# RGB_LED_Beta1.net
KiCad netlist of a schematic drawn in Altium Designer
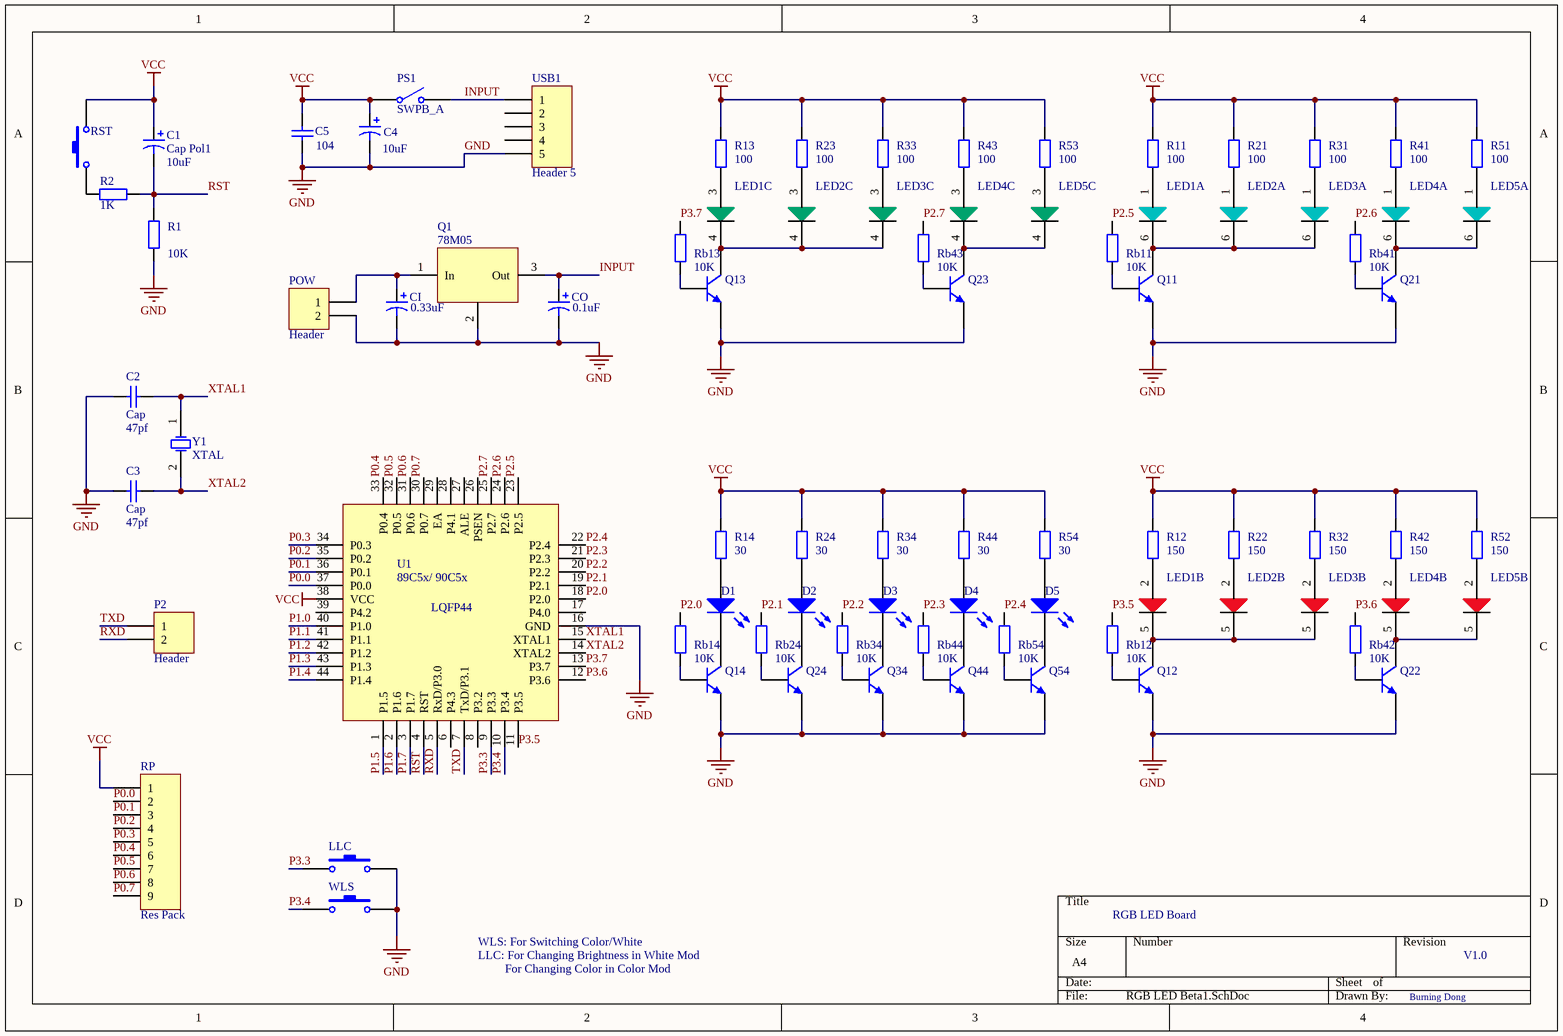
[diagram p0: RGB LED Beta1.SchDoc]

(export (version "E")
  (design (tool "Eeschema 10.0.6"))
  (components
    (comp (ref "C1")
      (value "Cap Pol1")
      (footprint "C0805")
      (description "Polarized Capacitor (Radial)")
      (fields (field (name "ALTIUM_VALUE") "10uF") (field (name "PUBLISHER") "Altium Limited"))
      (libsource (lib "Miscellaneous Devices") (part "Cap Pol1"))
    )
    (comp (ref "C2")
      (value "Cap")
      (footprint "C0805")
      (description "Capacitor")
      (fields (field (name "ALTIUM_VALUE") "47pf") (field (name "PUBLISHER") "Altium Limited"))
      (libsource (lib "Miscellaneous Devices") (part "Cap"))
    )
    (comp (ref "C3")
      (value "Cap")
      (footprint "C0805")
      (description "Capacitor")
      (fields (field (name "ALTIUM_VALUE") "47pf") (field (name "PUBLISHER") "Altium Limited"))
      (libsource (lib "Miscellaneous Devices") (part "Cap"))
    )
    (comp (ref "C4")
      (value "10uF")
      (footprint "C0805")
      (description "Polarized Capacitor (Radial)")
      (fields (field (name "Comment") "Cap Pol1") (field (name "PUBLISHER") "Altium Limited"))
      (libsource (lib "Miscellaneous Devices") (part "Cap Pol1"))
    )
    (comp (ref "C5")
      (value "104")
      (footprint "C1206")
      (description "Capacitor")
      (fields (field (name "Comment") "Cap") (field (name "PUBLISHER") "Altium Limited"))
      (libsource (lib "Miscellaneous Devices") (part "Cap"))
    )
    (comp (ref "CI")
      (value "0.33uF")
      (footprint "C0805")
      (description "Polarized Capacitor (Radial)")
      (fields (field (name "Comment") "Cap Pol1") (field (name "PUBLISHER") "Altium Limited"))
      (libsource (lib "Miscellaneous Devices") (part "Cap Pol1"))
    )
    (comp (ref "CO")
      (value "0.1uF")
      (footprint "C0805")
      (description "Polarized Capacitor (Radial)")
      (fields (field (name "Comment") "Cap Pol1") (field (name "PUBLISHER") "Altium Limited"))
      (libsource (lib "Miscellaneous Devices") (part "Cap Pol1"))
    )
    (comp (ref "D1")
      (value "LED0")
      (footprint "LED 5050 NoneRGB")
      (description "Typical INFRARED GaAs LED")
      (fields (field (name "PUBLISHER") "Altium Limited"))
      (libsource (lib "Miscellaneous Devices") (part "LED0"))
    )
    (comp (ref "D2")
      (value "LED0")
      (footprint "LED 5050 NoneRGB")
      (description "Typical INFRARED GaAs LED")
      (fields (field (name "PUBLISHER") "Altium Limited"))
      (libsource (lib "Miscellaneous Devices") (part "LED0"))
    )
    (comp (ref "D3")
      (value "LED0")
      (footprint "LED 5050 NoneRGB")
      (description "Typical INFRARED GaAs LED")
      (fields (field (name "PUBLISHER") "Altium Limited"))
      (libsource (lib "Miscellaneous Devices") (part "LED0"))
    )
    (comp (ref "D4")
      (value "LED0")
      (footprint "LED 5050 NoneRGB")
      (description "Typical INFRARED GaAs LED")
      (fields (field (name "PUBLISHER") "Altium Limited"))
      (libsource (lib "Miscellaneous Devices") (part "LED0"))
    )
    (comp (ref "D5")
      (value "LED0")
      (footprint "LED 5050 NoneRGB")
      (description "Typical INFRARED GaAs LED")
      (fields (field (name "PUBLISHER") "Altium Limited"))
      (libsource (lib "Miscellaneous Devices") (part "LED0"))
    )
    (comp (ref "LED1") (value "RGB LED") (footprint "LED 5050") (libsource (lib "Usual") (part "RGB LED")))
    (comp (ref "LED2") (value "RGB LED") (footprint "LED 5050") (libsource (lib "Usual") (part "RGB LED")))
    (comp (ref "LED3") (value "RGB LED") (footprint "LED 5050") (libsource (lib "Usual") (part "RGB LED")))
    (comp (ref "LED4") (value "RGB LED") (footprint "LED 5050") (libsource (lib "Usual") (part "RGB LED")))
    (comp (ref "LED5") (value "RGB LED") (footprint "LED 5050") (libsource (lib "Usual") (part "RGB LED")))
    (comp (ref "LLC")
      (value "SW-PB")
      (footprint "SW_A")
      (description "Switch")
      (fields (field (name "PUBLISHER") "Altium Limited"))
      (libsource (lib "Miscellaneous Devices") (part "SW-PB"))
    )
    (comp (ref "P2")
      (value "Header")
      (footprint "HDR1X2")
      (description "Header, 2-Pin")
      (fields (field (name "PUBLISHER") "Altium Limited"))
      (libsource (lib "") (part "Header 2_1"))
    )
    (comp (ref "POW")
      (value "Header")
      (footprint "HDR1X2")
      (description "Header, 2-Pin")
      (fields (field (name "PUBLISHER") "Altium Limited"))
      (libsource (lib "Miscellaneous Connectors") (part "Header 2"))
    )
    (comp (ref "PS1")
      (value "SWPB_A")
      (footprint "SW_B")
      (description "Single-Pole, Single-Throw Switch")
      (fields (field (name "PUBLISHER") "Altium Limited"))
      (libsource (lib "Miscellaneous Devices") (part "SW-SPST"))
    )
    (comp (ref "Q1") (value "78M05") (footprint "TO_252") (libsource (lib "Usual") (part "78XX")))
    (comp (ref "Q11")
      (value "s8050")
      (footprint "SOT-23_A_N")
      (description "NPN General Purpose Amplifier")
      (fields (field (name "PUBLISHER") "Altium Limited"))
      (libsource (lib "Miscellaneous Devices") (part "2N3904"))
    )
    (comp (ref "Q12")
      (value "s8050")
      (footprint "SOT-23_A_N")
      (description "NPN General Purpose Amplifier")
      (fields (field (name "PUBLISHER") "Altium Limited"))
      (libsource (lib "Miscellaneous Devices") (part "2N3904"))
    )
    (comp (ref "Q13")
      (value "s8050")
      (footprint "SOT-23_A_N")
      (description "NPN General Purpose Amplifier")
      (fields (field (name "PUBLISHER") "Altium Limited"))
      (libsource (lib "Miscellaneous Devices") (part "2N3904"))
    )
    (comp (ref "Q14")
      (value "s8050")
      (footprint "SOT-23_A_N")
      (description "NPN General Purpose Amplifier")
      (fields (field (name "PUBLISHER") "Altium Limited"))
      (libsource (lib "Miscellaneous Devices") (part "2N3904"))
    )
    (comp (ref "Q21")
      (value "s8050")
      (footprint "SOT-23_A_N")
      (description "NPN General Purpose Amplifier")
      (fields (field (name "PUBLISHER") "Altium Limited"))
      (libsource (lib "Miscellaneous Devices") (part "2N3904"))
    )
    (comp (ref "Q22")
      (value "s8050")
      (footprint "SOT-23_A_N")
      (description "NPN General Purpose Amplifier")
      (fields (field (name "PUBLISHER") "Altium Limited"))
      (libsource (lib "Miscellaneous Devices") (part "2N3904"))
    )
    (comp (ref "Q23")
      (value "s8050")
      (footprint "SOT-23_A_N")
      (description "NPN General Purpose Amplifier")
      (fields (field (name "PUBLISHER") "Altium Limited"))
      (libsource (lib "Miscellaneous Devices") (part "2N3904"))
    )
    (comp (ref "Q24")
      (value "s8050")
      (footprint "SOT-23_A_N")
      (description "NPN General Purpose Amplifier")
      (fields (field (name "PUBLISHER") "Altium Limited"))
      (libsource (lib "Miscellaneous Devices") (part "2N3904"))
    )
    (comp (ref "Q34")
      (value "s8050")
      (footprint "SOT-23_A_N")
      (description "NPN General Purpose Amplifier")
      (fields (field (name "PUBLISHER") "Altium Limited"))
      (libsource (lib "Miscellaneous Devices") (part "2N3904"))
    )
    (comp (ref "Q44")
      (value "s8050")
      (footprint "SOT-23_A_N")
      (description "NPN General Purpose Amplifier")
      (fields (field (name "PUBLISHER") "Altium Limited"))
      (libsource (lib "Miscellaneous Devices") (part "2N3904"))
    )
    (comp (ref "Q54")
      (value "s8050")
      (footprint "SOT-23_A_N")
      (description "NPN General Purpose Amplifier")
      (fields (field (name "PUBLISHER") "Altium Limited"))
      (libsource (lib "Miscellaneous Devices") (part "2N3904"))
    )
    (comp (ref "R1")
      (value "10K")
      (footprint "6-0805_N")
      (description "Resistor")
      (fields (field (name "Comment") "Res2") (field (name "PUBLISHER") "Altium Limited"))
      (libsource (lib "Miscellaneous Devices") (part "Res2"))
    )
    (comp (ref "R2")
      (value "1K")
      (footprint "6-0805_N")
      (description "Resistor")
      (fields (field (name "Comment") "Res2") (field (name "PUBLISHER") "Altium Limited"))
      (libsource (lib "") (part "Res2_1"))
    )
    (comp (ref "R11")
      (value "100")
      (footprint "6-0805_N")
      (description "Resistor")
      (fields (field (name "Comment") "Res2") (field (name "PUBLISHER") "Altium Limited"))
      (libsource (lib "Miscellaneous Devices") (part "Res2"))
    )
    (comp (ref "R12")
      (value "150")
      (footprint "6-0805_N")
      (description "Resistor")
      (fields (field (name "Comment") "Res2") (field (name "PUBLISHER") "Altium Limited"))
      (libsource (lib "Miscellaneous Devices") (part "Res2"))
    )
    (comp (ref "R13")
      (value "100")
      (footprint "6-0805_N")
      (description "Resistor")
      (fields (field (name "Comment") "Res2") (field (name "PUBLISHER") "Altium Limited"))
      (libsource (lib "Miscellaneous Devices") (part "Res2"))
    )
    (comp (ref "R14")
      (value "30")
      (footprint "6-0805_N")
      (description "Resistor")
      (fields (field (name "Comment") "Res2") (field (name "PUBLISHER") "Altium Limited"))
      (libsource (lib "Miscellaneous Devices") (part "Res2"))
    )
    (comp (ref "R21")
      (value "100")
      (footprint "6-0805_N")
      (description "Resistor")
      (fields (field (name "Comment") "Res2") (field (name "PUBLISHER") "Altium Limited"))
      (libsource (lib "Miscellaneous Devices") (part "Res2"))
    )
    (comp (ref "R22")
      (value "150")
      (footprint "6-0805_N")
      (description "Resistor")
      (fields (field (name "Comment") "Res2") (field (name "PUBLISHER") "Altium Limited"))
      (libsource (lib "Miscellaneous Devices") (part "Res2"))
    )
    (comp (ref "R23")
      (value "100")
      (footprint "6-0805_N")
      (description "Resistor")
      (fields (field (name "Comment") "Res2") (field (name "PUBLISHER") "Altium Limited"))
      (libsource (lib "Miscellaneous Devices") (part "Res2"))
    )
    (comp (ref "R24")
      (value "30")
      (footprint "6-0805_N")
      (description "Resistor")
      (fields (field (name "Comment") "Res2") (field (name "PUBLISHER") "Altium Limited"))
      (libsource (lib "Miscellaneous Devices") (part "Res2"))
    )
    (comp (ref "R31")
      (value "100")
      (footprint "6-0805_N")
      (description "Resistor")
      (fields (field (name "Comment") "Res2") (field (name "PUBLISHER") "Altium Limited"))
      (libsource (lib "Miscellaneous Devices") (part "Res2"))
    )
    (comp (ref "R32")
      (value "150")
      (footprint "6-0805_N")
      (description "Resistor")
      (fields (field (name "Comment") "Res2") (field (name "PUBLISHER") "Altium Limited"))
      (libsource (lib "Miscellaneous Devices") (part "Res2"))
    )
    (comp (ref "R33")
      (value "100")
      (footprint "6-0805_N")
      (description "Resistor")
      (fields (field (name "Comment") "Res2") (field (name "PUBLISHER") "Altium Limited"))
      (libsource (lib "Miscellaneous Devices") (part "Res2"))
    )
    (comp (ref "R34")
      (value "30")
      (footprint "6-0805_N")
      (description "Resistor")
      (fields (field (name "Comment") "Res2") (field (name "PUBLISHER") "Altium Limited"))
      (libsource (lib "Miscellaneous Devices") (part "Res2"))
    )
    (comp (ref "R41")
      (value "100")
      (footprint "6-0805_N")
      (description "Resistor")
      (fields (field (name "Comment") "Res2") (field (name "PUBLISHER") "Altium Limited"))
      (libsource (lib "Miscellaneous Devices") (part "Res2"))
    )
    (comp (ref "R42")
      (value "150")
      (footprint "6-0805_N")
      (description "Resistor")
      (fields (field (name "Comment") "Res2") (field (name "PUBLISHER") "Altium Limited"))
      (libsource (lib "Miscellaneous Devices") (part "Res2"))
    )
    (comp (ref "R43")
      (value "100")
      (footprint "6-0805_N")
      (description "Resistor")
      (fields (field (name "Comment") "Res2") (field (name "PUBLISHER") "Altium Limited"))
      (libsource (lib "Miscellaneous Devices") (part "Res2"))
    )
    (comp (ref "R44")
      (value "30")
      (footprint "6-0805_N")
      (description "Resistor")
      (fields (field (name "Comment") "Res2") (field (name "PUBLISHER") "Altium Limited"))
      (libsource (lib "Miscellaneous Devices") (part "Res2"))
    )
    (comp (ref "R51")
      (value "100")
      (footprint "6-0805_N")
      (description "Resistor")
      (fields (field (name "Comment") "Res2") (field (name "PUBLISHER") "Altium Limited"))
      (libsource (lib "Miscellaneous Devices") (part "Res2"))
    )
    (comp (ref "R52")
      (value "150")
      (footprint "6-0805_N")
      (description "Resistor")
      (fields (field (name "Comment") "Res2") (field (name "PUBLISHER") "Altium Limited"))
      (libsource (lib "Miscellaneous Devices") (part "Res2"))
    )
    (comp (ref "R53")
      (value "100")
      (footprint "6-0805_N")
      (description "Resistor")
      (fields (field (name "Comment") "Res2") (field (name "PUBLISHER") "Altium Limited"))
      (libsource (lib "Miscellaneous Devices") (part "Res2"))
    )
    (comp (ref "R54")
      (value "30")
      (footprint "6-0805_N")
      (description "Resistor")
      (fields (field (name "Comment") "Res2") (field (name "PUBLISHER") "Altium Limited"))
      (libsource (lib "Miscellaneous Devices") (part "Res2"))
    )
    (comp (ref "Rb11")
      (value "10K")
      (footprint "6-0805_N")
      (description "Resistor")
      (fields (field (name "Comment") "Res2") (field (name "PUBLISHER") "Altium Limited"))
      (libsource (lib "Miscellaneous Devices") (part "Res2"))
    )
    (comp (ref "Rb12")
      (value "10K")
      (footprint "6-0805_N")
      (description "Resistor")
      (fields (field (name "Comment") "Res2") (field (name "PUBLISHER") "Altium Limited"))
      (libsource (lib "Miscellaneous Devices") (part "Res2"))
    )
    (comp (ref "Rb13")
      (value "10K")
      (footprint "6-0805_N")
      (description "Resistor")
      (fields (field (name "Comment") "Res2") (field (name "PUBLISHER") "Altium Limited"))
      (libsource (lib "Miscellaneous Devices") (part "Res2"))
    )
    (comp (ref "Rb14")
      (value "10K")
      (footprint "6-0805_N")
      (description "Resistor")
      (fields (field (name "Comment") "Res2") (field (name "PUBLISHER") "Altium Limited"))
      (libsource (lib "Miscellaneous Devices") (part "Res2"))
    )
    (comp (ref "Rb24")
      (value "10K")
      (footprint "6-0805_N")
      (description "Resistor")
      (fields (field (name "Comment") "Res2") (field (name "PUBLISHER") "Altium Limited"))
      (libsource (lib "Miscellaneous Devices") (part "Res2"))
    )
    (comp (ref "Rb34")
      (value "10K")
      (footprint "6-0805_N")
      (description "Resistor")
      (fields (field (name "Comment") "Res2") (field (name "PUBLISHER") "Altium Limited"))
      (libsource (lib "Miscellaneous Devices") (part "Res2"))
    )
    (comp (ref "Rb41")
      (value "10K")
      (footprint "6-0805_N")
      (description "Resistor")
      (fields (field (name "Comment") "Res2") (field (name "PUBLISHER") "Altium Limited"))
      (libsource (lib "Miscellaneous Devices") (part "Res2"))
    )
    (comp (ref "Rb42")
      (value "10K")
      (footprint "6-0805_N")
      (description "Resistor")
      (fields (field (name "Comment") "Res2") (field (name "PUBLISHER") "Altium Limited"))
      (libsource (lib "Miscellaneous Devices") (part "Res2"))
    )
    (comp (ref "Rb43")
      (value "10K")
      (footprint "6-0805_N")
      (description "Resistor")
      (fields (field (name "Comment") "Res2") (field (name "PUBLISHER") "Altium Limited"))
      (libsource (lib "Miscellaneous Devices") (part "Res2"))
    )
    (comp (ref "Rb44")
      (value "10K")
      (footprint "6-0805_N")
      (description "Resistor")
      (fields (field (name "Comment") "Res2") (field (name "PUBLISHER") "Altium Limited"))
      (libsource (lib "Miscellaneous Devices") (part "Res2"))
    )
    (comp (ref "Rb54")
      (value "10K")
      (footprint "6-0805_N")
      (description "Resistor")
      (fields (field (name "Comment") "Res2") (field (name "PUBLISHER") "Altium Limited"))
      (libsource (lib "Miscellaneous Devices") (part "Res2"))
    )
    (comp (ref "RP")
      (value "Res Pack")
      (footprint "HDR1X9")
      (description "Header, 9-Pin")
      (fields (field (name "PUBLISHER") "Altium Limited"))
      (libsource (lib "Miscellaneous Connectors") (part "Header 9"))
    )
    (comp (ref "RST")
      (value "SW-PB")
      (footprint "SW_A")
      (description "Switch")
      (fields (field (name "PUBLISHER") "Altium Limited"))
      (libsource (lib "Miscellaneous Devices") (part "SW-PB"))
    )
    (comp (ref "U1")
      (value "89C5x/ 90C5x")
      (footprint "TQFP44_N")
      (libsource (lib "STC") (part "89C5x/ 90C5x"))
    )
    (comp (ref "USB1")
      (value "Header 5")
      (footprint "Micro_USB_B")
      (description "Header, 5-Pin")
      (fields (field (name "PUBLISHER") "Altium Limited"))
      (libsource (lib "Miscellaneous Connectors") (part "Header 5"))
    )
    (comp (ref "WLS")
      (value "SW-PB")
      (footprint "SW_A")
      (description "Switch")
      (fields (field (name "PUBLISHER") "Altium Limited"))
      (libsource (lib "Miscellaneous Devices") (part "SW-PB"))
    )
    (comp (ref "Y1")
      (value "XTAL")
      (footprint "XTAL")
      (description "Crystal Oscillator")
      (fields (field (name "PUBLISHER") "Altium Limited"))
      (libsource (lib "Miscellaneous Devices") (part "XTAL"))
    )
  )
  (nets
    (net (code "1") (name "/INPUT") (class "Default")
      (node (ref "CO") (pin "1") (pinfunction "1_1") (pintype "passive"))
      (node (ref "PS1") (pin "2") (pinfunction "NO_2") (pintype "passive"))
      (node (ref "Q1") (pin "3") (pinfunction "Out_3") (pintype "passive"))
      (node (ref "USB1") (pin "1") (pinfunction "1_1") (pintype "passive"))
    )
    (net (code "2") (name "/P0.0") (class "Default")
      (node (ref "RP") (pin "2") (pinfunction "2_2") (pintype "passive"))
      (node (ref "U1") (pin "37") (pinfunction "P0.0_37") (pintype "passive"))
    )
    (net (code "3") (name "/P0.1") (class "Default")
      (node (ref "RP") (pin "3") (pinfunction "3_3") (pintype "passive"))
      (node (ref "U1") (pin "36") (pinfunction "P0.1_36") (pintype "passive"))
    )
    (net (code "4") (name "/P0.2") (class "Default")
      (node (ref "RP") (pin "4") (pinfunction "4_4") (pintype "passive"))
      (node (ref "U1") (pin "35") (pinfunction "P0.2_35") (pintype "passive"))
    )
    (net (code "5") (name "/P0.3") (class "Default")
      (node (ref "RP") (pin "5") (pinfunction "5_5") (pintype "passive"))
      (node (ref "U1") (pin "34") (pinfunction "P0.3_34") (pintype "passive"))
    )
    (net (code "6") (name "/P0.4") (class "Default")
      (node (ref "RP") (pin "6") (pinfunction "6_6") (pintype "passive"))
      (node (ref "U1") (pin "33") (pinfunction "P0.4_33") (pintype "passive"))
    )
    (net (code "7") (name "/P0.5") (class "Default")
      (node (ref "RP") (pin "7") (pinfunction "7_7") (pintype "passive"))
      (node (ref "U1") (pin "32") (pinfunction "P0.5_32") (pintype "passive"))
    )
    (net (code "8") (name "/P0.6") (class "Default")
      (node (ref "RP") (pin "8") (pinfunction "8_8") (pintype "passive"))
      (node (ref "U1") (pin "31") (pinfunction "P0.6_31") (pintype "passive"))
    )
    (net (code "9") (name "/P0.7") (class "Default")
      (node (ref "RP") (pin "9") (pinfunction "9_9") (pintype "passive"))
      (node (ref "U1") (pin "30") (pinfunction "P0.7_30") (pintype "passive"))
    )
    (net (code "10") (name "/P1.0") (class "Default")
      (node (ref "U1") (pin "40") (pinfunction "P1.0_40") (pintype "passive"))
    )
    (net (code "11") (name "/P1.1") (class "Default")
      (node (ref "U1") (pin "41") (pinfunction "P1.1_41") (pintype "passive"))
    )
    (net (code "12") (name "/P1.2") (class "Default")
      (node (ref "U1") (pin "42") (pinfunction "P1.2_42") (pintype "passive"))
    )
    (net (code "13") (name "/P1.3") (class "Default")
      (node (ref "U1") (pin "43") (pinfunction "P1.3_43") (pintype "passive"))
    )
    (net (code "14") (name "/P1.4") (class "Default")
      (node (ref "U1") (pin "44") (pinfunction "P1.4_44") (pintype "passive"))
    )
    (net (code "15") (name "/P1.5") (class "Default")
      (node (ref "U1") (pin "1") (pinfunction "P1.5_1") (pintype "passive"))
    )
    (net (code "16") (name "/P1.6") (class "Default")
      (node (ref "U1") (pin "2") (pinfunction "P1.6_2") (pintype "passive"))
    )
    (net (code "17") (name "/P1.7") (class "Default")
      (node (ref "U1") (pin "3") (pinfunction "P1.7_3") (pintype "passive"))
    )
    (net (code "18") (name "/P2.0") (class "Default")
      (node (ref "Rb14") (pin "1") (pinfunction "1_1") (pintype "passive"))
      (node (ref "U1") (pin "18") (pinfunction "P2.0_18") (pintype "passive"))
    )
    (net (code "19") (name "/P2.1") (class "Default")
      (node (ref "Rb24") (pin "1") (pinfunction "1_1") (pintype "passive"))
      (node (ref "U1") (pin "19") (pinfunction "P2.1_19") (pintype "passive"))
    )
    (net (code "20") (name "/P2.2") (class "Default")
      (node (ref "Rb34") (pin "1") (pinfunction "1_1") (pintype "passive"))
      (node (ref "U1") (pin "20") (pinfunction "P2.2_20") (pintype "passive"))
    )
    (net (code "21") (name "/P2.3") (class "Default")
      (node (ref "Rb44") (pin "1") (pinfunction "1_1") (pintype "passive"))
      (node (ref "U1") (pin "21") (pinfunction "P2.3_21") (pintype "passive"))
    )
    (net (code "22") (name "/P2.4") (class "Default")
      (node (ref "Rb54") (pin "1") (pinfunction "1_1") (pintype "passive"))
      (node (ref "U1") (pin "22") (pinfunction "P2.4_22") (pintype "passive"))
    )
    (net (code "23") (name "/P2.5") (class "Default")
      (node (ref "Rb11") (pin "1") (pinfunction "1_1") (pintype "passive"))
      (node (ref "U1") (pin "23") (pinfunction "P2.5_23") (pintype "passive"))
    )
    (net (code "24") (name "/P2.6") (class "Default")
      (node (ref "Rb41") (pin "1") (pinfunction "1_1") (pintype "passive"))
      (node (ref "U1") (pin "24") (pinfunction "P2.6_24") (pintype "passive"))
    )
    (net (code "25") (name "/P2.7") (class "Default")
      (node (ref "Rb43") (pin "1") (pinfunction "1_1") (pintype "passive"))
      (node (ref "U1") (pin "25") (pinfunction "P2.7_25") (pintype "passive"))
    )
    (net (code "26") (name "/P3.3") (class "Default")
      (node (ref "LLC") (pin "1") (pinfunction "1_1") (pintype "passive"))
      (node (ref "U1") (pin "9") (pinfunction "P3.3_9") (pintype "passive"))
    )
    (net (code "27") (name "/P3.4") (class "Default")
      (node (ref "U1") (pin "10") (pinfunction "P3.4_10") (pintype "passive"))
      (node (ref "WLS") (pin "1") (pinfunction "1_1") (pintype "passive"))
    )
    (net (code "28") (name "/P3.5") (class "Default")
      (node (ref "Rb12") (pin "1") (pinfunction "1_1") (pintype "passive"))
      (node (ref "U1") (pin "11") (pinfunction "P3.5_11") (pintype "passive"))
    )
    (net (code "29") (name "/P3.6") (class "Default")
      (node (ref "Rb42") (pin "1") (pinfunction "1_1") (pintype "passive"))
      (node (ref "U1") (pin "12") (pinfunction "P3.6_12") (pintype "passive"))
    )
    (net (code "30") (name "/P3.7") (class "Default")
      (node (ref "Rb13") (pin "1") (pinfunction "1_1") (pintype "passive"))
      (node (ref "U1") (pin "13") (pinfunction "P3.7_13") (pintype "passive"))
    )
    (net (code "31") (name "/RST") (class "Default")
      (node (ref "C1") (pin "2") (pinfunction "2_2") (pintype "passive"))
      (node (ref "R1") (pin "1") (pinfunction "1_1") (pintype "passive"))
      (node (ref "R2") (pin "1") (pinfunction "1_1") (pintype "passive"))
      (node (ref "U1") (pin "4") (pinfunction "RST_4") (pintype "passive"))
    )
    (net (code "32") (name "/RXD") (class "Default")
      (node (ref "P2") (pin "2") (pinfunction "2_2") (pintype "passive"))
      (node (ref "U1") (pin "5") (pinfunction "RxD/P3.0_5") (pintype "passive"))
    )
    (net (code "33") (name "/TXD") (class "Default")
      (node (ref "P2") (pin "1") (pinfunction "1_1") (pintype "passive"))
      (node (ref "U1") (pin "7") (pinfunction "TxD/P3.1_7") (pintype "passive"))
    )
    (net (code "34") (name "/XTAL1") (class "Default")
      (node (ref "C2") (pin "2") (pinfunction "2_2") (pintype "passive"))
      (node (ref "U1") (pin "15") (pinfunction "XTAL1_15") (pintype "passive"))
      (node (ref "Y1") (pin "1") (pinfunction "OSC1_1") (pintype "passive"))
    )
    (net (code "35") (name "/XTAL2") (class "Default")
      (node (ref "C3") (pin "2") (pinfunction "2_2") (pintype "passive"))
      (node (ref "U1") (pin "14") (pinfunction "XTAL2_14") (pintype "passive"))
      (node (ref "Y1") (pin "2") (pinfunction "OSC2_2") (pintype "passive"))
    )
    (net (code "36") (name "GND") (class "Default")
      (node (ref "C2") (pin "1") (pinfunction "1_1") (pintype "passive"))
      (node (ref "C3") (pin "1") (pinfunction "1_1") (pintype "passive"))
      (node (ref "C4") (pin "2") (pinfunction "2_2") (pintype "passive"))
      (node (ref "C5") (pin "2") (pinfunction "2_2") (pintype "passive"))
      (node (ref "CI") (pin "2") (pinfunction "2_2") (pintype "passive"))
      (node (ref "CO") (pin "2") (pinfunction "2_2") (pintype "passive"))
      (node (ref "LLC") (pin "2") (pinfunction "2_2") (pintype "passive"))
      (node (ref "POW") (pin "2") (pinfunction "2_2") (pintype "passive"))
      (node (ref "Q1") (pin "2") (pinfunction "Com_2") (pintype "passive"))
      (node (ref "Q11") (pin "1") (pinfunction "E_1") (pintype "passive"))
      (node (ref "Q12") (pin "1") (pinfunction "E_1") (pintype "passive"))
      (node (ref "Q13") (pin "1") (pinfunction "E_1") (pintype "passive"))
      (node (ref "Q14") (pin "1") (pinfunction "E_1") (pintype "passive"))
      (node (ref "Q21") (pin "1") (pinfunction "E_1") (pintype "passive"))
      (node (ref "Q22") (pin "1") (pinfunction "E_1") (pintype "passive"))
      (node (ref "Q23") (pin "1") (pinfunction "E_1") (pintype "passive"))
      (node (ref "Q24") (pin "1") (pinfunction "E_1") (pintype "passive"))
      (node (ref "Q34") (pin "1") (pinfunction "E_1") (pintype "passive"))
      (node (ref "Q44") (pin "1") (pinfunction "E_1") (pintype "passive"))
      (node (ref "Q54") (pin "1") (pinfunction "E_1") (pintype "passive"))
      (node (ref "R1") (pin "2") (pinfunction "2_2") (pintype "passive"))
      (node (ref "U1") (pin "16") (pinfunction "GND_16") (pintype "passive"))
      (node (ref "USB1") (pin "5") (pinfunction "5_5") (pintype "passive"))
      (node (ref "WLS") (pin "2") (pinfunction "2_2") (pintype "passive"))
    )
    (net (code "37") (name "Net-(D1-A)") (class "Default")
      (node (ref "D1") (pin "1") (pinfunction "A_1") (pintype "passive"))
      (node (ref "R14") (pin "2") (pinfunction "2_2") (pintype "passive"))
    )
    (net (code "38") (name "Net-(D1-K)") (class "Default")
      (node (ref "D1") (pin "2") (pinfunction "K_2") (pintype "passive"))
      (node (ref "Q14") (pin "3") (pinfunction "C_3") (pintype "passive"))
    )
    (net (code "39") (name "Net-(D2-A)") (class "Default")
      (node (ref "D2") (pin "1") (pinfunction "A_1") (pintype "passive"))
      (node (ref "R24") (pin "2") (pinfunction "2_2") (pintype "passive"))
    )
    (net (code "40") (name "Net-(D2-K)") (class "Default")
      (node (ref "D2") (pin "2") (pinfunction "K_2") (pintype "passive"))
      (node (ref "Q24") (pin "3") (pinfunction "C_3") (pintype "passive"))
    )
    (net (code "41") (name "Net-(D3-A)") (class "Default")
      (node (ref "D3") (pin "1") (pinfunction "A_1") (pintype "passive"))
      (node (ref "R34") (pin "2") (pinfunction "2_2") (pintype "passive"))
    )
    (net (code "42") (name "Net-(D3-K)") (class "Default")
      (node (ref "D3") (pin "2") (pinfunction "K_2") (pintype "passive"))
      (node (ref "Q34") (pin "3") (pinfunction "C_3") (pintype "passive"))
    )
    (net (code "43") (name "Net-(D4-A)") (class "Default")
      (node (ref "D4") (pin "1") (pinfunction "A_1") (pintype "passive"))
      (node (ref "R44") (pin "2") (pinfunction "2_2") (pintype "passive"))
    )
    (net (code "44") (name "Net-(D4-K)") (class "Default")
      (node (ref "D4") (pin "2") (pinfunction "K_2") (pintype "passive"))
      (node (ref "Q44") (pin "3") (pinfunction "C_3") (pintype "passive"))
    )
    (net (code "45") (name "Net-(D5-A)") (class "Default")
      (node (ref "D5") (pin "1") (pinfunction "A_1") (pintype "passive"))
      (node (ref "R54") (pin "2") (pinfunction "2_2") (pintype "passive"))
    )
    (net (code "46") (name "Net-(D5-K)") (class "Default")
      (node (ref "D5") (pin "2") (pinfunction "K_2") (pintype "passive"))
      (node (ref "Q54") (pin "3") (pinfunction "C_3") (pintype "passive"))
    )
    (net (code "47") (name "Net-(LED1A-B+)") (class "Default")
      (node (ref "LED1") (pin "1") (pinfunction "B+_1") (pintype "passive"))
      (node (ref "R11") (pin "2") (pinfunction "2_2") (pintype "passive"))
    )
    (net (code "48") (name "Net-(LED1A-B-)") (class "Default")
      (node (ref "LED1") (pin "6") (pinfunction "B-_6") (pintype "passive"))
      (node (ref "LED2") (pin "6") (pinfunction "B-_6") (pintype "passive"))
      (node (ref "LED3") (pin "6") (pinfunction "B-_6") (pintype "passive"))
      (node (ref "Q11") (pin "3") (pinfunction "C_3") (pintype "passive"))
    )
    (net (code "49") (name "Net-(LED1B-B+)") (class "Default")
      (node (ref "LED1") (pin "2") (pinfunction "B+_2") (pintype "passive"))
      (node (ref "R12") (pin "2") (pinfunction "2_2") (pintype "passive"))
    )
    (net (code "50") (name "Net-(LED1B-B-)") (class "Default")
      (node (ref "LED1") (pin "5") (pinfunction "B-_5") (pintype "passive"))
      (node (ref "LED2") (pin "5") (pinfunction "B-_5") (pintype "passive"))
      (node (ref "LED3") (pin "5") (pinfunction "B-_5") (pintype "passive"))
      (node (ref "Q12") (pin "3") (pinfunction "C_3") (pintype "passive"))
    )
    (net (code "51") (name "Net-(LED1C-B+)") (class "Default")
      (node (ref "LED1") (pin "3") (pinfunction "B+_3") (pintype "passive"))
      (node (ref "R13") (pin "2") (pinfunction "2_2") (pintype "passive"))
    )
    (net (code "52") (name "Net-(LED1C-B-)") (class "Default")
      (node (ref "LED1") (pin "4") (pinfunction "B-_4") (pintype "passive"))
      (node (ref "LED2") (pin "4") (pinfunction "B-_4") (pintype "passive"))
      (node (ref "LED3") (pin "4") (pinfunction "B-_4") (pintype "passive"))
      (node (ref "Q13") (pin "3") (pinfunction "C_3") (pintype "passive"))
    )
    (net (code "53") (name "Net-(LED2A-B+)") (class "Default")
      (node (ref "LED2") (pin "1") (pinfunction "B+_1") (pintype "passive"))
      (node (ref "R21") (pin "2") (pinfunction "2_2") (pintype "passive"))
    )
    (net (code "54") (name "Net-(LED2B-B+)") (class "Default")
      (node (ref "LED2") (pin "2") (pinfunction "B+_2") (pintype "passive"))
      (node (ref "R22") (pin "2") (pinfunction "2_2") (pintype "passive"))
    )
    (net (code "55") (name "Net-(LED2C-B+)") (class "Default")
      (node (ref "LED2") (pin "3") (pinfunction "B+_3") (pintype "passive"))
      (node (ref "R23") (pin "2") (pinfunction "2_2") (pintype "passive"))
    )
    (net (code "56") (name "Net-(LED3A-B+)") (class "Default")
      (node (ref "LED3") (pin "1") (pinfunction "B+_1") (pintype "passive"))
      (node (ref "R31") (pin "2") (pinfunction "2_2") (pintype "passive"))
    )
    (net (code "57") (name "Net-(LED3B-B+)") (class "Default")
      (node (ref "LED3") (pin "2") (pinfunction "B+_2") (pintype "passive"))
      (node (ref "R32") (pin "2") (pinfunction "2_2") (pintype "passive"))
    )
    (net (code "58") (name "Net-(LED3C-B+)") (class "Default")
      (node (ref "LED3") (pin "3") (pinfunction "B+_3") (pintype "passive"))
      (node (ref "R33") (pin "2") (pinfunction "2_2") (pintype "passive"))
    )
    (net (code "59") (name "Net-(LED4A-B+)") (class "Default")
      (node (ref "LED4") (pin "1") (pinfunction "B+_1") (pintype "passive"))
      (node (ref "R41") (pin "2") (pinfunction "2_2") (pintype "passive"))
    )
    (net (code "60") (name "Net-(LED4A-B-)") (class "Default")
      (node (ref "LED4") (pin "6") (pinfunction "B-_6") (pintype "passive"))
      (node (ref "LED5") (pin "6") (pinfunction "B-_6") (pintype "passive"))
      (node (ref "Q21") (pin "3") (pinfunction "C_3") (pintype "passive"))
    )
    (net (code "61") (name "Net-(LED4B-B+)") (class "Default")
      (node (ref "LED4") (pin "2") (pinfunction "B+_2") (pintype "passive"))
      (node (ref "R42") (pin "2") (pinfunction "2_2") (pintype "passive"))
    )
    (net (code "62") (name "Net-(LED4B-B-)") (class "Default")
      (node (ref "LED4") (pin "5") (pinfunction "B-_5") (pintype "passive"))
      (node (ref "LED5") (pin "5") (pinfunction "B-_5") (pintype "passive"))
      (node (ref "Q22") (pin "3") (pinfunction "C_3") (pintype "passive"))
    )
    (net (code "63") (name "Net-(LED4C-B+)") (class "Default")
      (node (ref "LED4") (pin "3") (pinfunction "B+_3") (pintype "passive"))
      (node (ref "R43") (pin "2") (pinfunction "2_2") (pintype "passive"))
    )
    (net (code "64") (name "Net-(LED4C-B-)") (class "Default")
      (node (ref "LED4") (pin "4") (pinfunction "B-_4") (pintype "passive"))
      (node (ref "LED5") (pin "4") (pinfunction "B-_4") (pintype "passive"))
      (node (ref "Q23") (pin "3") (pinfunction "C_3") (pintype "passive"))
    )
    (net (code "65") (name "Net-(LED5A-B+)") (class "Default")
      (node (ref "LED5") (pin "1") (pinfunction "B+_1") (pintype "passive"))
      (node (ref "R51") (pin "2") (pinfunction "2_2") (pintype "passive"))
    )
    (net (code "66") (name "Net-(LED5B-B+)") (class "Default")
      (node (ref "LED5") (pin "2") (pinfunction "B+_2") (pintype "passive"))
      (node (ref "R52") (pin "2") (pinfunction "2_2") (pintype "passive"))
    )
    (net (code "67") (name "Net-(LED5C-B+)") (class "Default")
      (node (ref "LED5") (pin "3") (pinfunction "B+_3") (pintype "passive"))
      (node (ref "R53") (pin "2") (pinfunction "2_2") (pintype "passive"))
    )
    (net (code "68") (name "Net-(Q1-In)") (class "Default")
      (node (ref "CI") (pin "1") (pinfunction "1_1") (pintype "passive"))
      (node (ref "POW") (pin "1") (pinfunction "1_1") (pintype "passive"))
      (node (ref "Q1") (pin "1") (pinfunction "In_1") (pintype "passive"))
    )
    (net (code "69") (name "Net-(Q11-B)") (class "Default")
      (node (ref "Q11") (pin "2") (pinfunction "B_2") (pintype "passive"))
      (node (ref "Rb11") (pin "2") (pinfunction "2_2") (pintype "passive"))
    )
    (net (code "70") (name "Net-(Q12-B)") (class "Default")
      (node (ref "Q12") (pin "2") (pinfunction "B_2") (pintype "passive"))
      (node (ref "Rb12") (pin "2") (pinfunction "2_2") (pintype "passive"))
    )
    (net (code "71") (name "Net-(Q13-B)") (class "Default")
      (node (ref "Q13") (pin "2") (pinfunction "B_2") (pintype "passive"))
      (node (ref "Rb13") (pin "2") (pinfunction "2_2") (pintype "passive"))
    )
    (net (code "72") (name "Net-(Q14-B)") (class "Default")
      (node (ref "Q14") (pin "2") (pinfunction "B_2") (pintype "passive"))
      (node (ref "Rb14") (pin "2") (pinfunction "2_2") (pintype "passive"))
    )
    (net (code "73") (name "Net-(Q21-B)") (class "Default")
      (node (ref "Q21") (pin "2") (pinfunction "B_2") (pintype "passive"))
      (node (ref "Rb41") (pin "2") (pinfunction "2_2") (pintype "passive"))
    )
    (net (code "74") (name "Net-(Q22-B)") (class "Default")
      (node (ref "Q22") (pin "2") (pinfunction "B_2") (pintype "passive"))
      (node (ref "Rb42") (pin "2") (pinfunction "2_2") (pintype "passive"))
    )
    (net (code "75") (name "Net-(Q23-B)") (class "Default")
      (node (ref "Q23") (pin "2") (pinfunction "B_2") (pintype "passive"))
      (node (ref "Rb43") (pin "2") (pinfunction "2_2") (pintype "passive"))
    )
    (net (code "76") (name "Net-(Q24-B)") (class "Default")
      (node (ref "Q24") (pin "2") (pinfunction "B_2") (pintype "passive"))
      (node (ref "Rb24") (pin "2") (pinfunction "2_2") (pintype "passive"))
    )
    (net (code "77") (name "Net-(Q34-B)") (class "Default")
      (node (ref "Q34") (pin "2") (pinfunction "B_2") (pintype "passive"))
      (node (ref "Rb34") (pin "2") (pinfunction "2_2") (pintype "passive"))
    )
    (net (code "78") (name "Net-(Q44-B)") (class "Default")
      (node (ref "Q44") (pin "2") (pinfunction "B_2") (pintype "passive"))
      (node (ref "Rb44") (pin "2") (pinfunction "2_2") (pintype "passive"))
    )
    (net (code "79") (name "Net-(Q54-B)") (class "Default")
      (node (ref "Q54") (pin "2") (pinfunction "B_2") (pintype "passive"))
      (node (ref "Rb54") (pin "2") (pinfunction "2_2") (pintype "passive"))
    )
    (net (code "80") (name "Net-(R2-Pad2)") (class "Default")
      (node (ref "R2") (pin "2") (pinfunction "2_2") (pintype "passive"))
      (node (ref "RST") (pin "1") (pinfunction "1_1") (pintype "passive"))
    )
    (net (code "81") (name "VCC") (class "Default")
      (node (ref "C1") (pin "1") (pinfunction "1_1") (pintype "passive"))
      (node (ref "C4") (pin "1") (pinfunction "1_1") (pintype "passive"))
      (node (ref "C5") (pin "1") (pinfunction "1_1") (pintype "passive"))
      (node (ref "PS1") (pin "1") (pinfunction "COMMON_1") (pintype "passive"))
      (node (ref "R11") (pin "1") (pinfunction "1_1") (pintype "passive"))
      (node (ref "R12") (pin "1") (pinfunction "1_1") (pintype "passive"))
      (node (ref "R13") (pin "1") (pinfunction "1_1") (pintype "passive"))
      (node (ref "R14") (pin "1") (pinfunction "1_1") (pintype "passive"))
      (node (ref "R21") (pin "1") (pinfunction "1_1") (pintype "passive"))
      (node (ref "R22") (pin "1") (pinfunction "1_1") (pintype "passive"))
      (node (ref "R23") (pin "1") (pinfunction "1_1") (pintype "passive"))
      (node (ref "R24") (pin "1") (pinfunction "1_1") (pintype "passive"))
      (node (ref "R31") (pin "1") (pinfunction "1_1") (pintype "passive"))
      (node (ref "R32") (pin "1") (pinfunction "1_1") (pintype "passive"))
      (node (ref "R33") (pin "1") (pinfunction "1_1") (pintype "passive"))
      (node (ref "R34") (pin "1") (pinfunction "1_1") (pintype "passive"))
      (node (ref "R41") (pin "1") (pinfunction "1_1") (pintype "passive"))
      (node (ref "R42") (pin "1") (pinfunction "1_1") (pintype "passive"))
      (node (ref "R43") (pin "1") (pinfunction "1_1") (pintype "passive"))
      (node (ref "R44") (pin "1") (pinfunction "1_1") (pintype "passive"))
      (node (ref "R51") (pin "1") (pinfunction "1_1") (pintype "passive"))
      (node (ref "R52") (pin "1") (pinfunction "1_1") (pintype "passive"))
      (node (ref "R53") (pin "1") (pinfunction "1_1") (pintype "passive"))
      (node (ref "R54") (pin "1") (pinfunction "1_1") (pintype "passive"))
      (node (ref "RP") (pin "1") (pinfunction "1_1") (pintype "passive"))
      (node (ref "RST") (pin "2") (pinfunction "2_2") (pintype "passive"))
      (node (ref "U1") (pin "38") (pinfunction "VCC_38") (pintype "passive"))
    )
    (net (code "82") (name "unconnected-(U1-ALE-Pad27)") (class "Default")
      (node (ref "U1") (pin "27") (pinfunction "ALE_27") (pintype "passive"))
    )
    (net (code "83") (name "unconnected-(U1-EA-Pad29)") (class "Default")
      (node (ref "U1") (pin "29") (pinfunction "EA_29") (pintype "passive"))
    )
    (net (code "84") (name "unconnected-(U1-P3.2-Pad8)") (class "Default")
      (node (ref "U1") (pin "8") (pinfunction "P3.2_8") (pintype "passive"))
    )
    (net (code "85") (name "unconnected-(U1-P4.0-Pad17)") (class "Default")
      (node (ref "U1") (pin "17") (pinfunction "P4.0_17") (pintype "passive"))
    )
    (net (code "86") (name "unconnected-(U1-P4.1-Pad28)") (class "Default")
      (node (ref "U1") (pin "28") (pinfunction "P4.1_28") (pintype "passive"))
    )
    (net (code "87") (name "unconnected-(U1-P4.2-Pad39)") (class "Default")
      (node (ref "U1") (pin "39") (pinfunction "P4.2_39") (pintype "passive"))
    )
    (net (code "88") (name "unconnected-(U1-P4.3-Pad6)") (class "Default")
      (node (ref "U1") (pin "6") (pinfunction "P4.3_6") (pintype "passive"))
    )
    (net (code "89") (name "unconnected-(U1-PSEN-Pad26)") (class "Default")
      (node (ref "U1") (pin "26") (pinfunction "PSEN_26") (pintype "passive"))
    )
    (net (code "90") (name "unconnected-(USB1-Pad2)") (class "Default")
      (node (ref "USB1") (pin "2") (pinfunction "2_2") (pintype "passive"))
    )
    (net (code "91") (name "unconnected-(USB1-Pad3)") (class "Default")
      (node (ref "USB1") (pin "3") (pinfunction "3_3") (pintype "passive"))
    )
    (net (code "92") (name "unconnected-(USB1-Pad4)") (class "Default")
      (node (ref "USB1") (pin "4") (pinfunction "4_4") (pintype "passive"))
    )
  )
)
